# Matrix2.net
KiCad netlist of a schematic drawn in Altium Designer
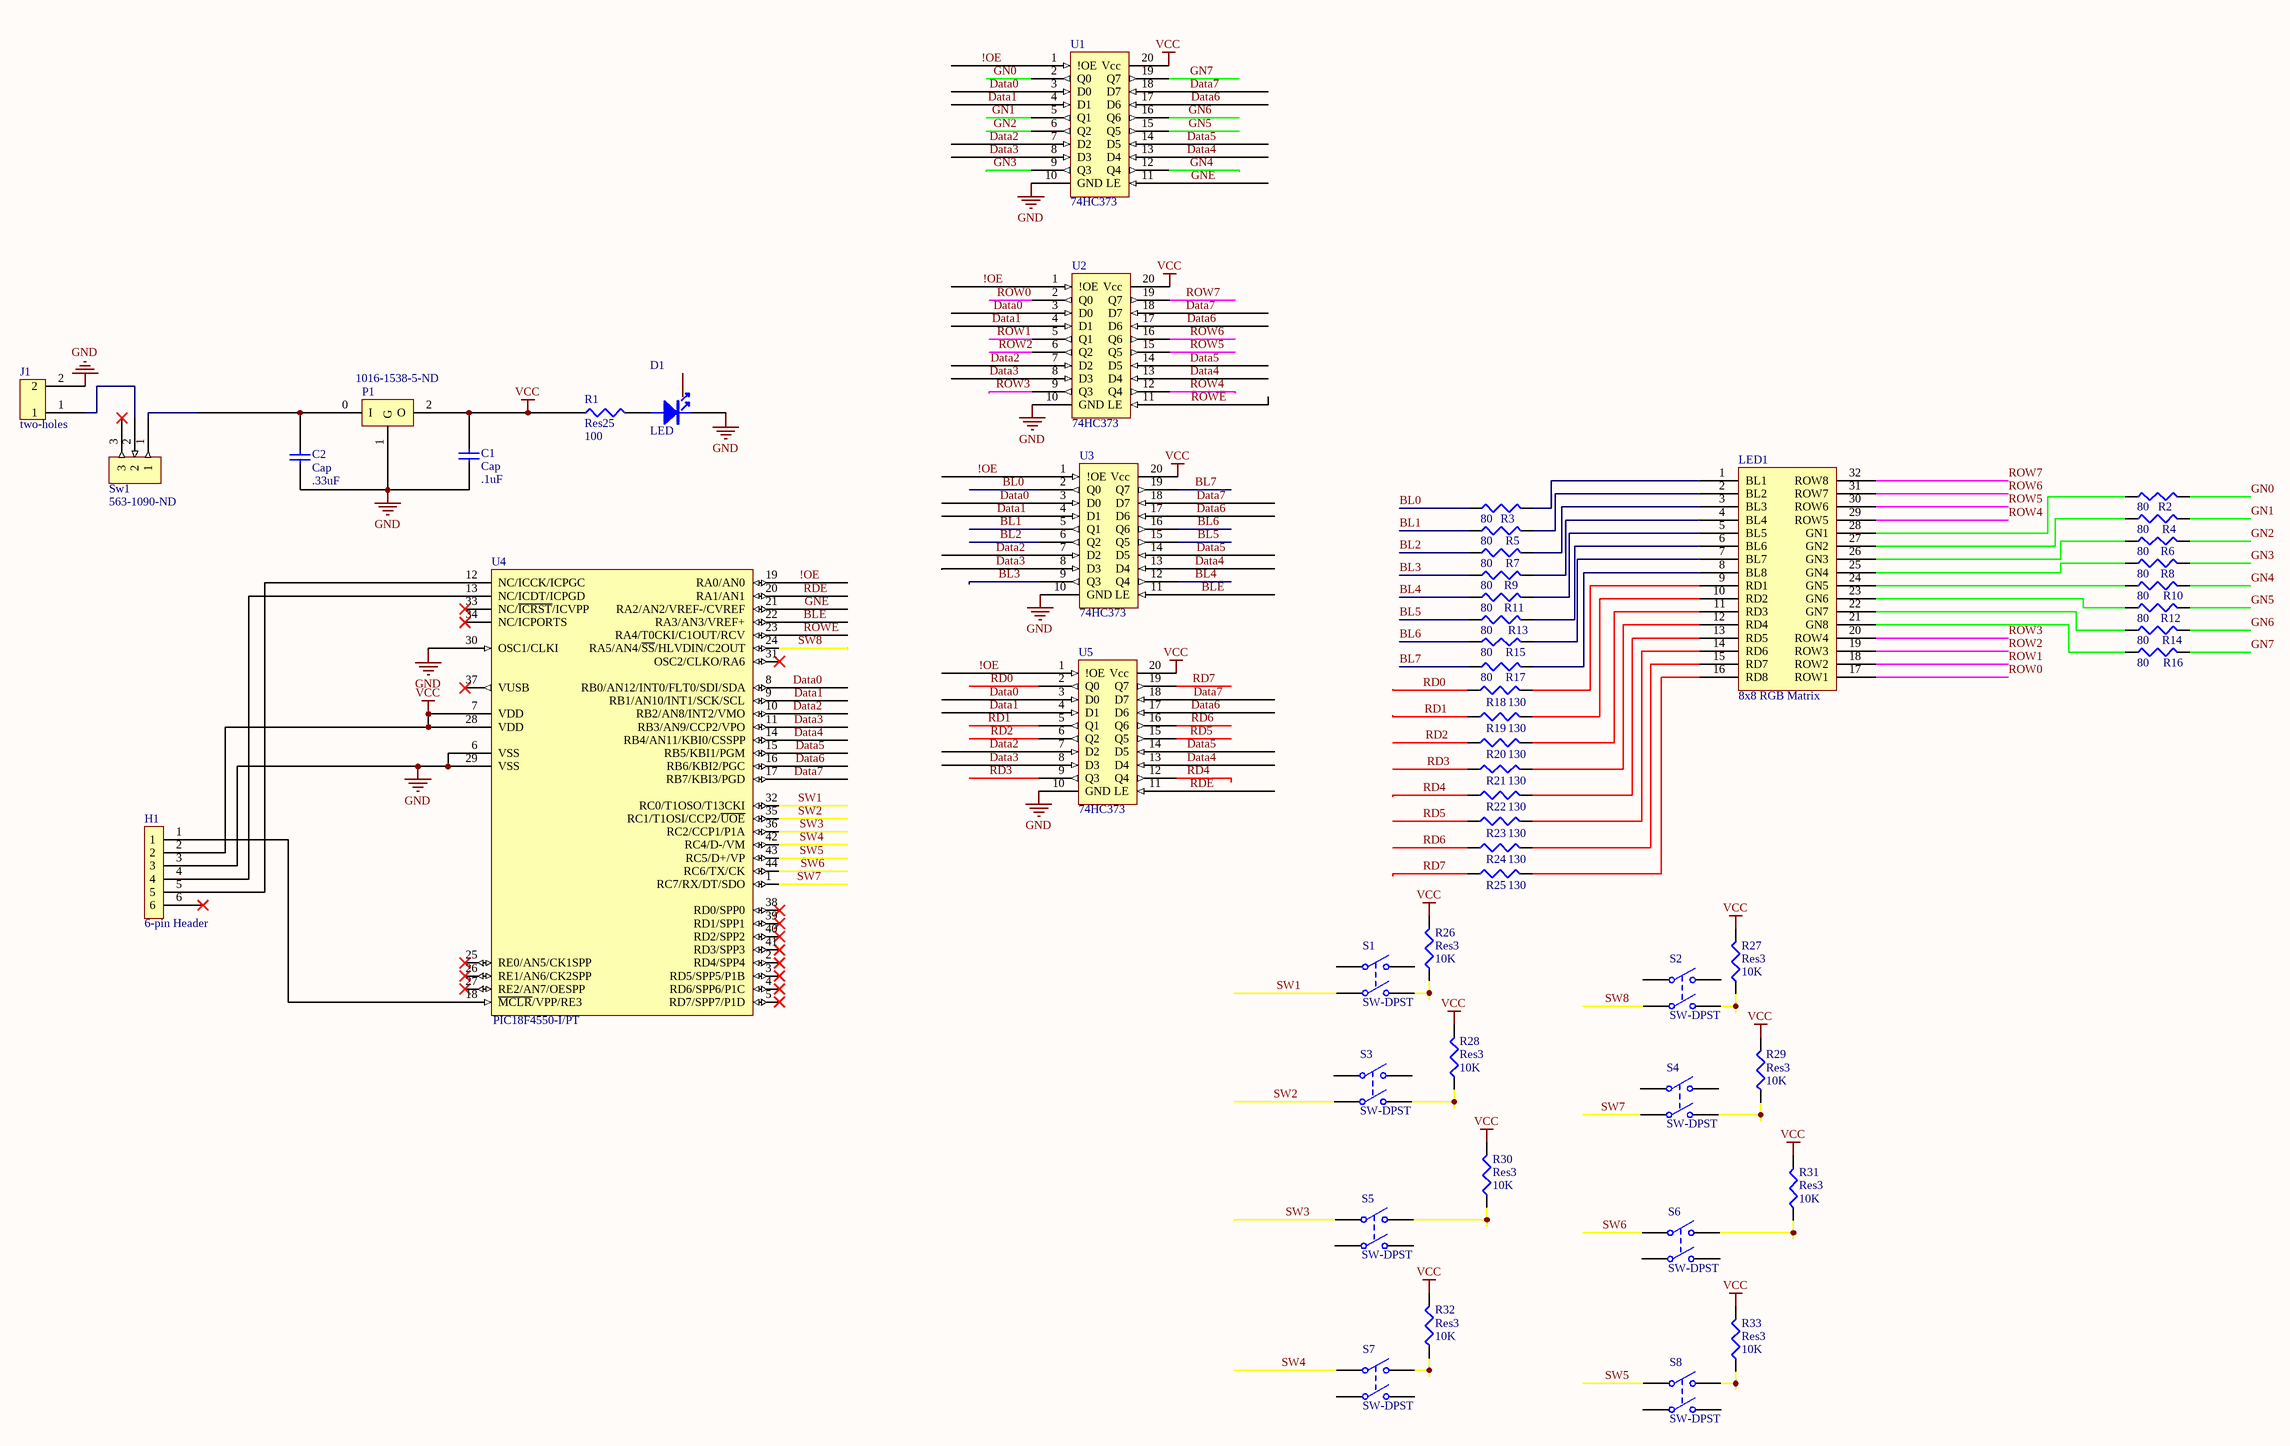
[diagram p0: Matrix2.SchDoc]

(export (version "E")
  (design (tool "Eeschema 10.0.6"))
  (components
    (comp (ref "C1")
      (value "Cap")
      (footprint "RAD-0.3")
      (description "Capacitor")
      (fields (field (name "ALTIUM_VALUE") ".1uF") (field (name "PUBLISHER") "Altium Limited"))
      (libsource (lib "Miscellaneous Devices") (part "Cap"))
    )
    (comp (ref "C2")
      (value "Cap")
      (footprint "RAD-0.3")
      (description "Capacitor")
      (fields (field (name "ALTIUM_VALUE") ".33uF") (field (name "PUBLISHER") "Altium Limited"))
      (libsource (lib "Miscellaneous Devices") (part "Cap"))
    )
    (comp (ref "D1")
      (value "LED")
      (footprint "LED-5608F")
      (description "Light Emitting Diode LED")
      (libsource (lib "ELEX130") (part "LED"))
    )
    (comp (ref "H1")
      (value "6-pin Header")
      (footprint "6-pin Header")
      (libsource (lib "Matrix") (part "6-pin Header"))
    )
    (comp (ref "J1")
      (value "two-holes")
      (footprint "two-holes")
      (libsource (lib "Matrix") (part "two-holes"))
    )
    (comp (ref "LED1")
      (value "8x8 RGB Matrix")
      (footprint "8x8 RGB Matrix")
      (libsource (lib "Matrix") (part "8x8 RGB Matrix"))
    )
    (comp (ref "P1")
      (value "1016-1538-5-ND")
      (footprint "1016-1538-5-ND")
      (libsource (lib "Matrix") (part "1016-1538-5-ND"))
    )
    (comp (ref "R1")
      (value "Res25")
      (footprint "J1-0603")
      (description "Resistor")
      (fields (field (name "ALTIUM_VALUE") "100") (field (name "PUBLISHER") "Altium Limited"))
      (libsource (lib "Miscellaneous Devices") (part "Res3"))
    )
    (comp (ref "R2") (value "80") (footprint "AXIAL0.5") (libsource (lib "ELEX283 (1)") (part "RES1")))
    (comp (ref "R3") (value "80") (footprint "AXIAL0.5") (libsource (lib "ELEX283 (1)") (part "RES1")))
    (comp (ref "R4") (value "80") (footprint "AXIAL0.5") (libsource (lib "ELEX283 (1)") (part "RES1")))
    (comp (ref "R5") (value "80") (footprint "AXIAL0.5") (libsource (lib "ELEX283 (1)") (part "RES1")))
    (comp (ref "R6") (value "80") (footprint "AXIAL0.5") (libsource (lib "ELEX283 (1)") (part "RES1")))
    (comp (ref "R7") (value "80") (footprint "AXIAL0.5") (libsource (lib "ELEX283 (1)") (part "RES1")))
    (comp (ref "R8") (value "80") (footprint "AXIAL0.5") (libsource (lib "ELEX283 (1)") (part "RES1")))
    (comp (ref "R9") (value "80") (footprint "AXIAL0.5") (libsource (lib "ELEX283 (1)") (part "RES1")))
    (comp (ref "R10") (value "80") (footprint "AXIAL0.5") (libsource (lib "ELEX283 (1)") (part "RES1")))
    (comp (ref "R11") (value "80") (footprint "AXIAL0.5") (libsource (lib "ELEX283 (1)") (part "RES1")))
    (comp (ref "R12") (value "80") (footprint "AXIAL0.5") (libsource (lib "ELEX283 (1)") (part "RES1")))
    (comp (ref "R13") (value "80") (footprint "AXIAL0.5") (libsource (lib "ELEX283 (1)") (part "RES1")))
    (comp (ref "R14") (value "80") (footprint "AXIAL0.5") (libsource (lib "ELEX283 (1)") (part "RES1")))
    (comp (ref "R15") (value "80") (footprint "AXIAL0.5") (libsource (lib "ELEX283 (1)") (part "RES1")))
    (comp (ref "R16") (value "80") (footprint "AXIAL0.5") (libsource (lib "ELEX283 (1)") (part "RES1")))
    (comp (ref "R17") (value "80") (footprint "AXIAL0.5") (libsource (lib "ELEX283 (1)") (part "RES1")))
    (comp (ref "R18")
      (value "130")
      (footprint "J1-0603")
      (description "Resistor")
      (fields (field (name "Comment") "Res3") (field (name "PUBLISHER") "Altium Limited"))
      (libsource (lib "Miscellaneous Devices") (part "Res3"))
    )
    (comp (ref "R19")
      (value "130")
      (footprint "J1-0603")
      (description "Resistor")
      (fields (field (name "Comment") "Res3") (field (name "PUBLISHER") "Altium Limited"))
      (libsource (lib "Miscellaneous Devices") (part "Res3"))
    )
    (comp (ref "R20")
      (value "130")
      (footprint "J1-0603")
      (description "Resistor")
      (fields (field (name "Comment") "Res3") (field (name "PUBLISHER") "Altium Limited"))
      (libsource (lib "Miscellaneous Devices") (part "Res3"))
    )
    (comp (ref "R21")
      (value "130")
      (footprint "J1-0603")
      (description "Resistor")
      (fields (field (name "Comment") "Res3") (field (name "PUBLISHER") "Altium Limited"))
      (libsource (lib "Miscellaneous Devices") (part "Res3"))
    )
    (comp (ref "R22")
      (value "130")
      (footprint "J1-0603")
      (description "Resistor")
      (fields (field (name "Comment") "Res3") (field (name "PUBLISHER") "Altium Limited"))
      (libsource (lib "Miscellaneous Devices") (part "Res3"))
    )
    (comp (ref "R23")
      (value "130")
      (footprint "J1-0603")
      (description "Resistor")
      (fields (field (name "Comment") "Res3") (field (name "PUBLISHER") "Altium Limited"))
      (libsource (lib "Miscellaneous Devices") (part "Res3"))
    )
    (comp (ref "R24")
      (value "130")
      (footprint "J1-0603")
      (description "Resistor")
      (fields (field (name "Comment") "Res3") (field (name "PUBLISHER") "Altium Limited"))
      (libsource (lib "Miscellaneous Devices") (part "Res3"))
    )
    (comp (ref "R25")
      (value "130")
      (footprint "J1-0603")
      (description "Resistor")
      (fields (field (name "Comment") "Res3") (field (name "PUBLISHER") "Altium Limited"))
      (libsource (lib "Miscellaneous Devices") (part "Res3"))
    )
    (comp (ref "R26")
      (value "Res3")
      (footprint "J1-0603")
      (description "Resistor")
      (fields (field (name "ALTIUM_VALUE") "10K") (field (name "PUBLISHER") "Altium Limited"))
      (libsource (lib "Miscellaneous Devices") (part "Res3"))
    )
    (comp (ref "R27")
      (value "Res3")
      (footprint "J1-0603")
      (description "Resistor")
      (fields (field (name "ALTIUM_VALUE") "10K") (field (name "PUBLISHER") "Altium Limited"))
      (libsource (lib "Miscellaneous Devices") (part "Res3"))
    )
    (comp (ref "R28")
      (value "Res3")
      (footprint "J1-0603")
      (description "Resistor")
      (fields (field (name "ALTIUM_VALUE") "10K") (field (name "PUBLISHER") "Altium Limited"))
      (libsource (lib "Miscellaneous Devices") (part "Res3"))
    )
    (comp (ref "R29")
      (value "Res3")
      (footprint "J1-0603")
      (description "Resistor")
      (fields (field (name "ALTIUM_VALUE") "10K") (field (name "PUBLISHER") "Altium Limited"))
      (libsource (lib "Miscellaneous Devices") (part "Res3"))
    )
    (comp (ref "R30")
      (value "Res3")
      (footprint "J1-0603")
      (description "Resistor")
      (fields (field (name "ALTIUM_VALUE") "10K") (field (name "PUBLISHER") "Altium Limited"))
      (libsource (lib "Miscellaneous Devices") (part "Res3"))
    )
    (comp (ref "R31")
      (value "Res3")
      (footprint "J1-0603")
      (description "Resistor")
      (fields (field (name "ALTIUM_VALUE") "10K") (field (name "PUBLISHER") "Altium Limited"))
      (libsource (lib "Miscellaneous Devices") (part "Res3"))
    )
    (comp (ref "R32")
      (value "Res3")
      (footprint "J1-0603")
      (description "Resistor")
      (fields (field (name "ALTIUM_VALUE") "10K") (field (name "PUBLISHER") "Altium Limited"))
      (libsource (lib "Miscellaneous Devices") (part "Res3"))
    )
    (comp (ref "R33")
      (value "Res3")
      (footprint "J1-0603")
      (description "Resistor")
      (fields (field (name "ALTIUM_VALUE") "10K") (field (name "PUBLISHER") "Altium Limited"))
      (libsource (lib "Miscellaneous Devices") (part "Res3"))
    )
    (comp (ref "S1")
      (value "SW-DPST")
      (footprint "DPST-4")
      (description "Double-Pole, Single-Throw Switch")
      (fields (field (name "PUBLISHER") "Altium Limited"))
      (libsource (lib "Miscellaneous Devices") (part "SW-DPST"))
    )
    (comp (ref "S2")
      (value "SW-DPST")
      (footprint "DPST-4")
      (description "Double-Pole, Single-Throw Switch")
      (fields (field (name "PUBLISHER") "Altium Limited"))
      (libsource (lib "Miscellaneous Devices") (part "SW-DPST"))
    )
    (comp (ref "S3")
      (value "SW-DPST")
      (footprint "DPST-4")
      (description "Double-Pole, Single-Throw Switch")
      (fields (field (name "PUBLISHER") "Altium Limited"))
      (libsource (lib "Miscellaneous Devices") (part "SW-DPST"))
    )
    (comp (ref "S4")
      (value "SW-DPST")
      (footprint "DPST-4")
      (description "Double-Pole, Single-Throw Switch")
      (fields (field (name "PUBLISHER") "Altium Limited"))
      (libsource (lib "Miscellaneous Devices") (part "SW-DPST"))
    )
    (comp (ref "S5")
      (value "SW-DPST")
      (footprint "DPST-4")
      (description "Double-Pole, Single-Throw Switch")
      (fields (field (name "PUBLISHER") "Altium Limited"))
      (libsource (lib "Miscellaneous Devices") (part "SW-DPST"))
    )
    (comp (ref "S6")
      (value "SW-DPST")
      (footprint "DPST-4")
      (description "Double-Pole, Single-Throw Switch")
      (fields (field (name "PUBLISHER") "Altium Limited"))
      (libsource (lib "Miscellaneous Devices") (part "SW-DPST"))
    )
    (comp (ref "S7")
      (value "SW-DPST")
      (footprint "DPST-4")
      (description "Double-Pole, Single-Throw Switch")
      (fields (field (name "PUBLISHER") "Altium Limited"))
      (libsource (lib "Miscellaneous Devices") (part "SW-DPST"))
    )
    (comp (ref "S8")
      (value "SW-DPST")
      (footprint "DPST-4")
      (description "Double-Pole, Single-Throw Switch")
      (fields (field (name "PUBLISHER") "Altium Limited"))
      (libsource (lib "Miscellaneous Devices") (part "SW-DPST"))
    )
    (comp (ref "Sw1")
      (value "563-1090-ND")
      (footprint "563-1090-ND")
      (libsource (lib "Matrix") (part "563-1090-ND"))
    )
    (comp (ref "U1") (value "74HC373") (footprint "74HC373") (libsource (lib "Matrix") (part "74HC373")))
    (comp (ref "U2") (value "74HC373") (footprint "74HC373") (libsource (lib "Matrix") (part "74HC373")))
    (comp (ref "U3") (value "74HC373") (footprint "74HC373") (libsource (lib "Matrix") (part "74HC373")))
    (comp (ref "U4")
      (value "PIC18F4550-I/PT")
      (footprint "TQFP-PT44_N")
      (fields (field (name "PUBLISHER") "Altium Limited"))
      (libsource (lib "Microchip Microcontroller 8-Bit PIC18") (part "PIC18F4550-I/PT"))
    )
    (comp (ref "U5") (value "74HC373") (footprint "74HC373") (libsource (lib "Matrix") (part "74HC373")))
  )
  (nets
    (net (code "1") (name "/!OE") (class "Default")
      (node (ref "U1") (pin "1") (pinfunction "!OE_1") (pintype "input"))
      (node (ref "U2") (pin "1") (pinfunction "!OE_1") (pintype "input"))
      (node (ref "U3") (pin "1") (pinfunction "!OE_1") (pintype "input"))
      (node (ref "U4") (pin "19") (pinfunction "RA0/AN0_19") (pintype "bidirectional"))
      (node (ref "U5") (pin "1") (pinfunction "!OE_1") (pintype "input"))
    )
    (net (code "2") (name "/BL0") (class "Default")
      (node (ref "R3") (pin "1") (pintype "passive"))
      (node (ref "U3") (pin "2") (pinfunction "Q0_2") (pintype "output"))
    )
    (net (code "3") (name "/BL1") (class "Default")
      (node (ref "R5") (pin "1") (pintype "passive"))
      (node (ref "U3") (pin "5") (pinfunction "Q1_5") (pintype "output"))
    )
    (net (code "4") (name "/BL2") (class "Default")
      (node (ref "R7") (pin "1") (pintype "passive"))
      (node (ref "U3") (pin "6") (pinfunction "Q2_6") (pintype "output"))
    )
    (net (code "5") (name "/BL3") (class "Default")
      (node (ref "R9") (pin "1") (pintype "passive"))
      (node (ref "U3") (pin "9") (pinfunction "Q3_9") (pintype "output"))
    )
    (net (code "6") (name "/BL4") (class "Default")
      (node (ref "R11") (pin "1") (pintype "passive"))
      (node (ref "U3") (pin "12") (pinfunction "Q4_12") (pintype "output"))
    )
    (net (code "7") (name "/BL5") (class "Default")
      (node (ref "R13") (pin "1") (pintype "passive"))
      (node (ref "U3") (pin "15") (pinfunction "Q5_15") (pintype "output"))
    )
    (net (code "8") (name "/BL6") (class "Default")
      (node (ref "R15") (pin "1") (pintype "passive"))
      (node (ref "U3") (pin "16") (pinfunction "Q6_16") (pintype "output"))
    )
    (net (code "9") (name "/BL7") (class "Default")
      (node (ref "R17") (pin "1") (pintype "passive"))
      (node (ref "U3") (pin "19") (pinfunction "Q7_19") (pintype "output"))
    )
    (net (code "10") (name "/BLE") (class "Default")
      (node (ref "U3") (pin "11") (pinfunction "LE_11") (pintype "input"))
      (node (ref "U4") (pin "22") (pinfunction "RA3/AN3/VREF+_22") (pintype "bidirectional"))
    )
    (net (code "11") (name "/Data0") (class "Default")
      (node (ref "U1") (pin "3") (pinfunction "D0_3") (pintype "input"))
      (node (ref "U2") (pin "3") (pinfunction "D0_3") (pintype "input"))
      (node (ref "U3") (pin "3") (pinfunction "D0_3") (pintype "input"))
      (node (ref "U4") (pin "8") (pinfunction "RB0/AN12/INT0/FLT0/SDI/SDA_8") (pintype "bidirectional"))
      (node (ref "U5") (pin "3") (pinfunction "D0_3") (pintype "input"))
    )
    (net (code "12") (name "/Data1") (class "Default")
      (node (ref "U1") (pin "4") (pinfunction "D1_4") (pintype "input"))
      (node (ref "U2") (pin "4") (pinfunction "D1_4") (pintype "input"))
      (node (ref "U3") (pin "4") (pinfunction "D1_4") (pintype "input"))
      (node (ref "U4") (pin "9") (pinfunction "RB1/AN10/INT1/SCK/SCL_9") (pintype "bidirectional"))
      (node (ref "U5") (pin "4") (pinfunction "D1_4") (pintype "input"))
    )
    (net (code "13") (name "/Data2") (class "Default")
      (node (ref "U1") (pin "7") (pinfunction "D2_7") (pintype "input"))
      (node (ref "U2") (pin "7") (pinfunction "D2_7") (pintype "input"))
      (node (ref "U3") (pin "7") (pinfunction "D2_7") (pintype "input"))
      (node (ref "U4") (pin "10") (pinfunction "RB2/AN8/INT2/VMO_10") (pintype "bidirectional"))
      (node (ref "U5") (pin "7") (pinfunction "D2_7") (pintype "input"))
    )
    (net (code "14") (name "/Data3") (class "Default")
      (node (ref "U1") (pin "8") (pinfunction "D3_8") (pintype "input"))
      (node (ref "U2") (pin "8") (pinfunction "D3_8") (pintype "input"))
      (node (ref "U3") (pin "8") (pinfunction "D3_8") (pintype "input"))
      (node (ref "U4") (pin "11") (pinfunction "RB3/AN9/CCP2/VPO_11") (pintype "bidirectional"))
      (node (ref "U5") (pin "8") (pinfunction "D3_8") (pintype "input"))
    )
    (net (code "15") (name "/Data4") (class "Default")
      (node (ref "U1") (pin "13") (pinfunction "D4_13") (pintype "input"))
      (node (ref "U2") (pin "13") (pinfunction "D4_13") (pintype "input"))
      (node (ref "U3") (pin "13") (pinfunction "D4_13") (pintype "input"))
      (node (ref "U4") (pin "14") (pinfunction "RB4/AN11/KBI0/CSSPP_14") (pintype "bidirectional"))
      (node (ref "U5") (pin "13") (pinfunction "D4_13") (pintype "input"))
    )
    (net (code "16") (name "/Data5") (class "Default")
      (node (ref "U1") (pin "14") (pinfunction "D5_14") (pintype "input"))
      (node (ref "U2") (pin "14") (pinfunction "D5_14") (pintype "input"))
      (node (ref "U3") (pin "14") (pinfunction "D5_14") (pintype "input"))
      (node (ref "U4") (pin "15") (pinfunction "RB5/KBI1/PGM_15") (pintype "bidirectional"))
      (node (ref "U5") (pin "14") (pinfunction "D5_14") (pintype "input"))
    )
    (net (code "17") (name "/Data6") (class "Default")
      (node (ref "U1") (pin "17") (pinfunction "D6_17") (pintype "input"))
      (node (ref "U2") (pin "17") (pinfunction "D6_17") (pintype "input"))
      (node (ref "U3") (pin "17") (pinfunction "D6_17") (pintype "input"))
      (node (ref "U4") (pin "16") (pinfunction "RB6/KBI2/PGC_16") (pintype "bidirectional"))
      (node (ref "U5") (pin "17") (pinfunction "D6_17") (pintype "input"))
    )
    (net (code "18") (name "/Data7") (class "Default")
      (node (ref "U1") (pin "18") (pinfunction "D7_18") (pintype "input"))
      (node (ref "U2") (pin "18") (pinfunction "D7_18") (pintype "input"))
      (node (ref "U3") (pin "18") (pinfunction "D7_18") (pintype "input"))
      (node (ref "U4") (pin "17") (pinfunction "RB7/KBI3/PGD_17") (pintype "bidirectional"))
      (node (ref "U5") (pin "18") (pinfunction "D7_18") (pintype "input"))
    )
    (net (code "19") (name "/GN0") (class "Default")
      (node (ref "R2") (pin "2") (pintype "passive"))
      (node (ref "U1") (pin "2") (pinfunction "Q0_2") (pintype "output"))
    )
    (net (code "20") (name "/GN1") (class "Default")
      (node (ref "R4") (pin "2") (pintype "passive"))
      (node (ref "U1") (pin "5") (pinfunction "Q1_5") (pintype "output"))
    )
    (net (code "21") (name "/GN2") (class "Default")
      (node (ref "R6") (pin "2") (pintype "passive"))
      (node (ref "U1") (pin "6") (pinfunction "Q2_6") (pintype "output"))
    )
    (net (code "22") (name "/GN3") (class "Default")
      (node (ref "R8") (pin "2") (pintype "passive"))
      (node (ref "U1") (pin "9") (pinfunction "Q3_9") (pintype "output"))
    )
    (net (code "23") (name "/GN4") (class "Default")
      (node (ref "R10") (pin "2") (pintype "passive"))
      (node (ref "U1") (pin "12") (pinfunction "Q4_12") (pintype "output"))
    )
    (net (code "24") (name "/GN5") (class "Default")
      (node (ref "R12") (pin "2") (pintype "passive"))
      (node (ref "U1") (pin "15") (pinfunction "Q5_15") (pintype "output"))
    )
    (net (code "25") (name "/GN6") (class "Default")
      (node (ref "R14") (pin "2") (pintype "passive"))
      (node (ref "U1") (pin "16") (pinfunction "Q6_16") (pintype "output"))
    )
    (net (code "26") (name "/GN7") (class "Default")
      (node (ref "R16") (pin "2") (pintype "passive"))
      (node (ref "U1") (pin "19") (pinfunction "Q7_19") (pintype "output"))
    )
    (net (code "27") (name "/GNE") (class "Default")
      (node (ref "U1") (pin "11") (pinfunction "LE_11") (pintype "input"))
      (node (ref "U4") (pin "21") (pinfunction "RA2/AN2/VREF-/CVREF_21") (pintype "bidirectional"))
    )
    (net (code "28") (name "/RD0") (class "Default")
      (node (ref "R18") (pin "1") (pinfunction "1_1") (pintype "passive"))
      (node (ref "U5") (pin "2") (pinfunction "Q0_2") (pintype "output"))
    )
    (net (code "29") (name "/RD1") (class "Default")
      (node (ref "R19") (pin "1") (pinfunction "1_1") (pintype "passive"))
      (node (ref "U5") (pin "5") (pinfunction "Q1_5") (pintype "output"))
    )
    (net (code "30") (name "/RD2") (class "Default")
      (node (ref "R20") (pin "1") (pinfunction "1_1") (pintype "passive"))
      (node (ref "U5") (pin "6") (pinfunction "Q2_6") (pintype "output"))
    )
    (net (code "31") (name "/RD3") (class "Default")
      (node (ref "R21") (pin "1") (pinfunction "1_1") (pintype "passive"))
      (node (ref "U5") (pin "9") (pinfunction "Q3_9") (pintype "output"))
    )
    (net (code "32") (name "/RD4") (class "Default")
      (node (ref "R22") (pin "1") (pinfunction "1_1") (pintype "passive"))
      (node (ref "U5") (pin "12") (pinfunction "Q4_12") (pintype "output"))
    )
    (net (code "33") (name "/RD5") (class "Default")
      (node (ref "R23") (pin "1") (pinfunction "1_1") (pintype "passive"))
      (node (ref "U5") (pin "15") (pinfunction "Q5_15") (pintype "output"))
    )
    (net (code "34") (name "/RD6") (class "Default")
      (node (ref "R24") (pin "1") (pinfunction "1_1") (pintype "passive"))
      (node (ref "U5") (pin "16") (pinfunction "Q6_16") (pintype "output"))
    )
    (net (code "35") (name "/RD7") (class "Default")
      (node (ref "R25") (pin "1") (pinfunction "1_1") (pintype "passive"))
      (node (ref "U5") (pin "19") (pinfunction "Q7_19") (pintype "output"))
    )
    (net (code "36") (name "/RDE") (class "Default")
      (node (ref "U4") (pin "20") (pinfunction "RA1/AN1_20") (pintype "bidirectional"))
      (node (ref "U5") (pin "11") (pinfunction "LE_11") (pintype "input"))
    )
    (net (code "37") (name "/ROW0") (class "Default")
      (node (ref "LED1") (pin "17") (pinfunction "ROW1_17") (pintype "passive"))
      (node (ref "U2") (pin "2") (pinfunction "Q0_2") (pintype "output"))
    )
    (net (code "38") (name "/ROW1") (class "Default")
      (node (ref "LED1") (pin "18") (pinfunction "ROW2_18") (pintype "passive"))
      (node (ref "U2") (pin "5") (pinfunction "Q1_5") (pintype "output"))
    )
    (net (code "39") (name "/ROW2") (class "Default")
      (node (ref "LED1") (pin "19") (pinfunction "ROW3_19") (pintype "passive"))
      (node (ref "U2") (pin "6") (pinfunction "Q2_6") (pintype "output"))
    )
    (net (code "40") (name "/ROW3") (class "Default")
      (node (ref "LED1") (pin "20") (pinfunction "ROW4_20") (pintype "passive"))
      (node (ref "U2") (pin "9") (pinfunction "Q3_9") (pintype "output"))
    )
    (net (code "41") (name "/ROW4") (class "Default")
      (node (ref "LED1") (pin "29") (pinfunction "ROW5_29") (pintype "passive"))
      (node (ref "U2") (pin "12") (pinfunction "Q4_12") (pintype "output"))
    )
    (net (code "42") (name "/ROW5") (class "Default")
      (node (ref "LED1") (pin "30") (pinfunction "ROW6_30") (pintype "passive"))
      (node (ref "U2") (pin "15") (pinfunction "Q5_15") (pintype "output"))
    )
    (net (code "43") (name "/ROW6") (class "Default")
      (node (ref "LED1") (pin "31") (pinfunction "ROW7_31") (pintype "passive"))
      (node (ref "U2") (pin "16") (pinfunction "Q6_16") (pintype "output"))
    )
    (net (code "44") (name "/ROW7") (class "Default")
      (node (ref "LED1") (pin "32") (pinfunction "ROW8_32") (pintype "passive"))
      (node (ref "U2") (pin "19") (pinfunction "Q7_19") (pintype "output"))
    )
    (net (code "45") (name "/ROWE") (class "Default")
      (node (ref "U2") (pin "11") (pinfunction "LE_11") (pintype "input"))
      (node (ref "U4") (pin "23") (pinfunction "RA4/T0CKI/C1OUT/RCV_23") (pintype "bidirectional"))
    )
    (net (code "46") (name "/SW1") (class "Default")
      (node (ref "S1") (pin "3") (pinfunction "COMMON2_3") (pintype "passive"))
      (node (ref "U4") (pin "32") (pinfunction "RC0/T1OSO/T13CKI_32") (pintype "bidirectional"))
    )
    (net (code "47") (name "/SW2") (class "Default")
      (node (ref "S3") (pin "3") (pinfunction "COMMON2_3") (pintype "passive"))
      (node (ref "U4") (pin "35") (pinfunction "RC1/T1OSI/CCP2/~{UOE}_35") (pintype "bidirectional"))
    )
    (net (code "48") (name "/SW3") (class "Default")
      (node (ref "S5") (pin "1") (pinfunction "COMMON1_1") (pintype "passive"))
      (node (ref "U4") (pin "36") (pinfunction "RC2/CCP1/P1A_36") (pintype "bidirectional"))
    )
    (net (code "49") (name "/SW4") (class "Default")
      (node (ref "S7") (pin "1") (pinfunction "COMMON1_1") (pintype "passive"))
      (node (ref "U4") (pin "42") (pinfunction "RC4/D-/VM_42") (pintype "bidirectional"))
    )
    (net (code "50") (name "/SW5") (class "Default")
      (node (ref "S8") (pin "1") (pinfunction "COMMON1_1") (pintype "passive"))
      (node (ref "U4") (pin "43") (pinfunction "RC5/D+/VP_43") (pintype "bidirectional"))
    )
    (net (code "51") (name "/SW6") (class "Default")
      (node (ref "S6") (pin "1") (pinfunction "COMMON1_1") (pintype "passive"))
      (node (ref "U4") (pin "44") (pinfunction "RC6/TX/CK_44") (pintype "bidirectional"))
    )
    (net (code "52") (name "/SW7") (class "Default")
      (node (ref "S4") (pin "3") (pinfunction "COMMON2_3") (pintype "passive"))
      (node (ref "U4") (pin "1") (pinfunction "RC7/RX/DT/SDO_1") (pintype "bidirectional"))
    )
    (net (code "53") (name "/SW8") (class "Default")
      (node (ref "S2") (pin "3") (pinfunction "COMMON2_3") (pintype "passive"))
      (node (ref "U4") (pin "24") (pinfunction "RA5/AN4/~{SS}/HLVDIN/C2OUT_24") (pintype "bidirectional"))
    )
    (net (code "54") (name "GND") (class "Default")
      (node (ref "C1") (pin "1") (pinfunction "1_1") (pintype "passive"))
      (node (ref "C2") (pin "1") (pinfunction "1_1") (pintype "passive"))
      (node (ref "D1") (pin "K") (pinfunction "K_K") (pintype "passive"))
      (node (ref "H1") (pin "3") (pinfunction "3_3") (pintype "passive"))
      (node (ref "J1") (pin "2") (pinfunction "2_2") (pintype "passive"))
      (node (ref "P1") (pin "1") (pinfunction "G_1") (pintype "passive"))
      (node (ref "U1") (pin "10") (pinfunction "GND_10") (pintype "passive"))
      (node (ref "U2") (pin "10") (pinfunction "GND_10") (pintype "passive"))
      (node (ref "U3") (pin "10") (pinfunction "GND_10") (pintype "passive"))
      (node (ref "U4") (pin "29") (pinfunction "VSS_29") (pintype "power_in"))
      (node (ref "U4") (pin "30") (pinfunction "OSC1/CLKI_30") (pintype "input"))
      (node (ref "U4") (pin "6") (pinfunction "VSS_6") (pintype "power_in"))
      (node (ref "U5") (pin "10") (pinfunction "GND_10") (pintype "passive"))
    )
    (net (code "55") (name "Net-(D1-PadA)") (class "Default")
      (node (ref "D1") (pin "A") (pinfunction "A_A") (pintype "passive"))
      (node (ref "R1") (pin "2") (pinfunction "2_2") (pintype "passive"))
    )
    (net (code "56") (name "Net-(J1-Pad1)") (class "Default")
      (node (ref "J1") (pin "1") (pinfunction "1_1") (pintype "passive"))
      (node (ref "Sw1") (pin "2") (pinfunction "2_2") (pintype "input"))
    )
    (net (code "57") (name "Net-(LED1-BL1)") (class "Default")
      (node (ref "LED1") (pin "1") (pinfunction "BL1_1") (pintype "passive"))
      (node (ref "R3") (pin "2") (pintype "passive"))
    )
    (net (code "58") (name "Net-(LED1-BL2)") (class "Default")
      (node (ref "LED1") (pin "2") (pinfunction "BL2_2") (pintype "passive"))
      (node (ref "R5") (pin "2") (pintype "passive"))
    )
    (net (code "59") (name "Net-(LED1-BL3)") (class "Default")
      (node (ref "LED1") (pin "3") (pinfunction "BL3_3") (pintype "passive"))
      (node (ref "R7") (pin "2") (pintype "passive"))
    )
    (net (code "60") (name "Net-(LED1-BL4)") (class "Default")
      (node (ref "LED1") (pin "4") (pinfunction "BL4_4") (pintype "passive"))
      (node (ref "R9") (pin "2") (pintype "passive"))
    )
    (net (code "61") (name "Net-(LED1-BL5)") (class "Default")
      (node (ref "LED1") (pin "5") (pinfunction "BL5_5") (pintype "passive"))
      (node (ref "R11") (pin "2") (pintype "passive"))
    )
    (net (code "62") (name "Net-(LED1-BL6)") (class "Default")
      (node (ref "LED1") (pin "6") (pinfunction "BL6_6") (pintype "passive"))
      (node (ref "R13") (pin "2") (pintype "passive"))
    )
    (net (code "63") (name "Net-(LED1-BL7)") (class "Default")
      (node (ref "LED1") (pin "7") (pinfunction "BL7_7") (pintype "passive"))
      (node (ref "R15") (pin "2") (pintype "passive"))
    )
    (net (code "64") (name "Net-(LED1-BL8)") (class "Default")
      (node (ref "LED1") (pin "8") (pinfunction "BL8_8") (pintype "passive"))
      (node (ref "R17") (pin "2") (pintype "passive"))
    )
    (net (code "65") (name "Net-(LED1-GN1)") (class "Default")
      (node (ref "LED1") (pin "28") (pinfunction "GN1_28") (pintype "passive"))
      (node (ref "R2") (pin "1") (pintype "passive"))
    )
    (net (code "66") (name "Net-(LED1-GN2)") (class "Default")
      (node (ref "LED1") (pin "27") (pinfunction "GN2_27") (pintype "passive"))
      (node (ref "R4") (pin "1") (pintype "passive"))
    )
    (net (code "67") (name "Net-(LED1-GN3)") (class "Default")
      (node (ref "LED1") (pin "26") (pinfunction "GN3_26") (pintype "passive"))
      (node (ref "R6") (pin "1") (pintype "passive"))
    )
    (net (code "68") (name "Net-(LED1-GN4)") (class "Default")
      (node (ref "LED1") (pin "25") (pinfunction "GN4_25") (pintype "passive"))
      (node (ref "R8") (pin "1") (pintype "passive"))
    )
    (net (code "69") (name "Net-(LED1-GN5)") (class "Default")
      (node (ref "LED1") (pin "24") (pinfunction "GN5_24") (pintype "passive"))
      (node (ref "R10") (pin "1") (pintype "passive"))
    )
    (net (code "70") (name "Net-(LED1-GN6)") (class "Default")
      (node (ref "LED1") (pin "23") (pinfunction "GN6_23") (pintype "passive"))
      (node (ref "R12") (pin "1") (pintype "passive"))
    )
    (net (code "71") (name "Net-(LED1-GN7)") (class "Default")
      (node (ref "LED1") (pin "22") (pinfunction "GN7_22") (pintype "passive"))
      (node (ref "R14") (pin "1") (pintype "passive"))
    )
    (net (code "72") (name "Net-(LED1-GN8)") (class "Default")
      (node (ref "LED1") (pin "21") (pinfunction "GN8_21") (pintype "passive"))
      (node (ref "R16") (pin "1") (pintype "passive"))
    )
    (net (code "73") (name "Net-(LED1-RD1)") (class "Default")
      (node (ref "LED1") (pin "9") (pinfunction "RD1_9") (pintype "passive"))
      (node (ref "R18") (pin "2") (pinfunction "2_2") (pintype "passive"))
    )
    (net (code "74") (name "Net-(LED1-RD2)") (class "Default")
      (node (ref "LED1") (pin "10") (pinfunction "RD2_10") (pintype "passive"))
      (node (ref "R19") (pin "2") (pinfunction "2_2") (pintype "passive"))
    )
    (net (code "75") (name "Net-(LED1-RD3)") (class "Default")
      (node (ref "LED1") (pin "11") (pinfunction "RD3_11") (pintype "passive"))
      (node (ref "R20") (pin "2") (pinfunction "2_2") (pintype "passive"))
    )
    (net (code "76") (name "Net-(LED1-RD4)") (class "Default")
      (node (ref "LED1") (pin "12") (pinfunction "RD4_12") (pintype "passive"))
      (node (ref "R21") (pin "2") (pinfunction "2_2") (pintype "passive"))
    )
    (net (code "77") (name "Net-(LED1-RD5)") (class "Default")
      (node (ref "LED1") (pin "13") (pinfunction "RD5_13") (pintype "passive"))
      (node (ref "R22") (pin "2") (pinfunction "2_2") (pintype "passive"))
    )
    (net (code "78") (name "Net-(LED1-RD6)") (class "Default")
      (node (ref "LED1") (pin "14") (pinfunction "RD6_14") (pintype "passive"))
      (node (ref "R23") (pin "2") (pinfunction "2_2") (pintype "passive"))
    )
    (net (code "79") (name "Net-(LED1-RD7)") (class "Default")
      (node (ref "LED1") (pin "15") (pinfunction "RD7_15") (pintype "passive"))
      (node (ref "R24") (pin "2") (pinfunction "2_2") (pintype "passive"))
    )
    (net (code "80") (name "Net-(LED1-RD8)") (class "Default")
      (node (ref "LED1") (pin "16") (pinfunction "RD8_16") (pintype "passive"))
      (node (ref "R25") (pin "2") (pinfunction "2_2") (pintype "passive"))
    )
    (net (code "81") (name "Net-(P1-I)") (class "Default")
      (node (ref "C2") (pin "2") (pinfunction "2_2") (pintype "passive"))
      (node (ref "P1") (pin "0") (pinfunction "I_0") (pintype "passive"))
      (node (ref "Sw1") (pin "1") (pinfunction "1_1") (pintype "output"))
    )
    (net (code "82") (name "Net-(S1-NO2)") (class "Default")
      (node (ref "R26") (pin "1") (pinfunction "1_1") (pintype "passive"))
      (node (ref "S1") (pin "4") (pinfunction "NO2_4") (pintype "passive"))
    )
    (net (code "83") (name "Net-(S2-NO2)") (class "Default")
      (node (ref "R27") (pin "1") (pinfunction "1_1") (pintype "passive"))
      (node (ref "S2") (pin "4") (pinfunction "NO2_4") (pintype "passive"))
    )
    (net (code "84") (name "Net-(S3-NO2)") (class "Default")
      (node (ref "R28") (pin "1") (pinfunction "1_1") (pintype "passive"))
      (node (ref "S3") (pin "4") (pinfunction "NO2_4") (pintype "passive"))
    )
    (net (code "85") (name "Net-(S4-NO2)") (class "Default")
      (node (ref "R29") (pin "1") (pinfunction "1_1") (pintype "passive"))
      (node (ref "S4") (pin "4") (pinfunction "NO2_4") (pintype "passive"))
    )
    (net (code "86") (name "Net-(S5-NO1)") (class "Default")
      (node (ref "R30") (pin "1") (pinfunction "1_1") (pintype "passive"))
      (node (ref "S5") (pin "2") (pinfunction "NO1_2") (pintype "passive"))
    )
    (net (code "87") (name "Net-(S6-NO1)") (class "Default")
      (node (ref "R31") (pin "1") (pinfunction "1_1") (pintype "passive"))
      (node (ref "S6") (pin "2") (pinfunction "NO1_2") (pintype "passive"))
    )
    (net (code "88") (name "Net-(S7-NO1)") (class "Default")
      (node (ref "R32") (pin "1") (pinfunction "1_1") (pintype "passive"))
      (node (ref "S7") (pin "2") (pinfunction "NO1_2") (pintype "passive"))
    )
    (net (code "89") (name "Net-(S8-NO1)") (class "Default")
      (node (ref "R33") (pin "1") (pinfunction "1_1") (pintype "passive"))
      (node (ref "S8") (pin "2") (pinfunction "NO1_2") (pintype "passive"))
    )
    (net (code "90") (name "Net-(U4-NC{slash}ICCK{slash}ICPGC)") (class "Default")
      (node (ref "H1") (pin "5") (pinfunction "5_5") (pintype "passive"))
      (node (ref "U4") (pin "12") (pinfunction "NC/ICCK/ICPGC_12") (pintype "passive"))
    )
    (net (code "91") (name "Net-(U4-NC{slash}ICDT{slash}ICPGD)") (class "Default")
      (node (ref "H1") (pin "4") (pinfunction "4_4") (pintype "passive"))
      (node (ref "U4") (pin "13") (pinfunction "NC/ICDT/ICPGD_13") (pintype "passive"))
    )
    (net (code "92") (name "Net-(U4-~{MCLR}{slash}VPP{slash}RE3)") (class "Default")
      (node (ref "H1") (pin "1") (pinfunction "1_1") (pintype "passive"))
      (node (ref "U4") (pin "18") (pinfunction "~{MCLR}/VPP/RE3_18") (pintype "input"))
    )
    (net (code "93") (name "VCC") (class "Default")
      (node (ref "C1") (pin "2") (pinfunction "2_2") (pintype "passive"))
      (node (ref "H1") (pin "2") (pinfunction "2_2") (pintype "passive"))
      (node (ref "P1") (pin "2") (pinfunction "O_2") (pintype "passive"))
      (node (ref "R1") (pin "1") (pinfunction "1_1") (pintype "passive"))
      (node (ref "R26") (pin "2") (pinfunction "2_2") (pintype "passive"))
      (node (ref "R27") (pin "2") (pinfunction "2_2") (pintype "passive"))
      (node (ref "R28") (pin "2") (pinfunction "2_2") (pintype "passive"))
      (node (ref "R29") (pin "2") (pinfunction "2_2") (pintype "passive"))
      (node (ref "R30") (pin "2") (pinfunction "2_2") (pintype "passive"))
      (node (ref "R31") (pin "2") (pinfunction "2_2") (pintype "passive"))
      (node (ref "R32") (pin "2") (pinfunction "2_2") (pintype "passive"))
      (node (ref "R33") (pin "2") (pinfunction "2_2") (pintype "passive"))
      (node (ref "U1") (pin "20") (pinfunction "Vcc_20") (pintype "power_in"))
      (node (ref "U2") (pin "20") (pinfunction "Vcc_20") (pintype "power_in"))
      (node (ref "U3") (pin "20") (pinfunction "Vcc_20") (pintype "power_in"))
      (node (ref "U4") (pin "28") (pinfunction "VDD_28") (pintype "power_in"))
      (node (ref "U4") (pin "7") (pinfunction "VDD_7") (pintype "power_in"))
      (node (ref "U5") (pin "20") (pinfunction "Vcc_20") (pintype "power_in"))
    )
    (net (code "94") (name "unconnected-(H1-Pad6)") (class "Default")
      (node (ref "H1") (pin "6") (pinfunction "6_6") (pintype "passive+no_connect"))
    )
    (net (code "95") (name "unconnected-(S1-COMMON1-Pad1)") (class "Default")
      (node (ref "S1") (pin "1") (pinfunction "COMMON1_1") (pintype "passive"))
    )
    (net (code "96") (name "unconnected-(S1-NO1-Pad2)") (class "Default")
      (node (ref "S1") (pin "2") (pinfunction "NO1_2") (pintype "passive"))
    )
    (net (code "97") (name "unconnected-(S2-COMMON1-Pad1)") (class "Default")
      (node (ref "S2") (pin "1") (pinfunction "COMMON1_1") (pintype "passive"))
    )
    (net (code "98") (name "unconnected-(S2-NO1-Pad2)") (class "Default")
      (node (ref "S2") (pin "2") (pinfunction "NO1_2") (pintype "passive"))
    )
    (net (code "99") (name "unconnected-(S3-COMMON1-Pad1)") (class "Default")
      (node (ref "S3") (pin "1") (pinfunction "COMMON1_1") (pintype "passive"))
    )
    (net (code "100") (name "unconnected-(S3-NO1-Pad2)") (class "Default")
      (node (ref "S3") (pin "2") (pinfunction "NO1_2") (pintype "passive"))
    )
    (net (code "101") (name "unconnected-(S4-COMMON1-Pad1)") (class "Default")
      (node (ref "S4") (pin "1") (pinfunction "COMMON1_1") (pintype "passive"))
    )
    (net (code "102") (name "unconnected-(S4-NO1-Pad2)") (class "Default")
      (node (ref "S4") (pin "2") (pinfunction "NO1_2") (pintype "passive"))
    )
    (net (code "103") (name "unconnected-(S5-COMMON2-Pad3)") (class "Default")
      (node (ref "S5") (pin "3") (pinfunction "COMMON2_3") (pintype "passive"))
    )
    (net (code "104") (name "unconnected-(S5-NO2-Pad4)") (class "Default")
      (node (ref "S5") (pin "4") (pinfunction "NO2_4") (pintype "passive"))
    )
    (net (code "105") (name "unconnected-(S6-COMMON2-Pad3)") (class "Default")
      (node (ref "S6") (pin "3") (pinfunction "COMMON2_3") (pintype "passive"))
    )
    (net (code "106") (name "unconnected-(S6-NO2-Pad4)") (class "Default")
      (node (ref "S6") (pin "4") (pinfunction "NO2_4") (pintype "passive"))
    )
    (net (code "107") (name "unconnected-(S7-COMMON2-Pad3)") (class "Default")
      (node (ref "S7") (pin "3") (pinfunction "COMMON2_3") (pintype "passive"))
    )
    (net (code "108") (name "unconnected-(S7-NO2-Pad4)") (class "Default")
      (node (ref "S7") (pin "4") (pinfunction "NO2_4") (pintype "passive"))
    )
    (net (code "109") (name "unconnected-(S8-COMMON2-Pad3)") (class "Default")
      (node (ref "S8") (pin "3") (pinfunction "COMMON2_3") (pintype "passive"))
    )
    (net (code "110") (name "unconnected-(S8-NO2-Pad4)") (class "Default")
      (node (ref "S8") (pin "4") (pinfunction "NO2_4") (pintype "passive"))
    )
    (net (code "111") (name "unconnected-(Sw1-Pad3)") (class "Default")
      (node (ref "Sw1") (pin "3") (pinfunction "3_3") (pintype "output+no_connect"))
    )
    (net (code "112") (name "unconnected-(U4-NC{slash}ICPORTS-Pad34)") (class "Default")
      (node (ref "U4") (pin "34") (pinfunction "NC/ICPORTS_34") (pintype "passive+no_connect"))
    )
    (net (code "113") (name "unconnected-(U4-NC{slash}~{ICRST}{slash}ICVPP-Pad33)") (class "Default")
      (node (ref "U4") (pin "33") (pinfunction "NC/~{ICRST}/ICVPP_33") (pintype "passive+no_connect"))
    )
    (net (code "114") (name "unconnected-(U4-OSC2{slash}CLKO{slash}RA6-Pad31)") (class "Default")
      (node (ref "U4") (pin "31") (pinfunction "OSC2/CLKO/RA6_31") (pintype "bidirectional+no_connect"))
    )
    (net (code "115") (name "unconnected-(U4-RD0{slash}SPP0-Pad38)") (class "Default")
      (node (ref "U4") (pin "38") (pinfunction "RD0/SPP0_38") (pintype "bidirectional+no_connect"))
    )
    (net (code "116") (name "unconnected-(U4-RD1{slash}SPP1-Pad39)") (class "Default")
      (node (ref "U4") (pin "39") (pinfunction "RD1/SPP1_39") (pintype "bidirectional+no_connect"))
    )
    (net (code "117") (name "unconnected-(U4-RD2{slash}SPP2-Pad40)") (class "Default")
      (node (ref "U4") (pin "40") (pinfunction "RD2/SPP2_40") (pintype "bidirectional+no_connect"))
    )
    (net (code "118") (name "unconnected-(U4-RD3{slash}SPP3-Pad41)") (class "Default")
      (node (ref "U4") (pin "41") (pinfunction "RD3/SPP3_41") (pintype "bidirectional+no_connect"))
    )
    (net (code "119") (name "unconnected-(U4-RD4{slash}SPP4-Pad2)") (class "Default")
      (node (ref "U4") (pin "2") (pinfunction "RD4/SPP4_2") (pintype "bidirectional+no_connect"))
    )
    (net (code "120") (name "unconnected-(U4-RD5{slash}SPP5{slash}P1B-Pad3)") (class "Default")
      (node (ref "U4") (pin "3") (pinfunction "RD5/SPP5/P1B_3") (pintype "bidirectional+no_connect"))
    )
    (net (code "121") (name "unconnected-(U4-RD6{slash}SPP6{slash}P1C-Pad4)") (class "Default")
      (node (ref "U4") (pin "4") (pinfunction "RD6/SPP6/P1C_4") (pintype "bidirectional+no_connect"))
    )
    (net (code "122") (name "unconnected-(U4-RD7{slash}SPP7{slash}P1D-Pad5)") (class "Default")
      (node (ref "U4") (pin "5") (pinfunction "RD7/SPP7/P1D_5") (pintype "bidirectional+no_connect"))
    )
    (net (code "123") (name "unconnected-(U4-RE0{slash}AN5{slash}CK1SPP-Pad25)") (class "Default")
      (node (ref "U4") (pin "25") (pinfunction "RE0/AN5/CK1SPP_25") (pintype "bidirectional+no_connect"))
    )
    (net (code "124") (name "unconnected-(U4-RE1{slash}AN6{slash}CK2SPP-Pad26)") (class "Default")
      (node (ref "U4") (pin "26") (pinfunction "RE1/AN6/CK2SPP_26") (pintype "bidirectional+no_connect"))
    )
    (net (code "125") (name "unconnected-(U4-RE2{slash}AN7{slash}OESPP-Pad27)") (class "Default")
      (node (ref "U4") (pin "27") (pinfunction "RE2/AN7/OESPP_27") (pintype "bidirectional+no_connect"))
    )
    (net (code "126") (name "unconnected-(U4-VUSB-Pad37)") (class "Default")
      (node (ref "U4") (pin "37") (pinfunction "VUSB_37") (pintype "output+no_connect"))
    )
  )
)
